# Power.net
KiCad netlist of a schematic drawn in Altium Designer
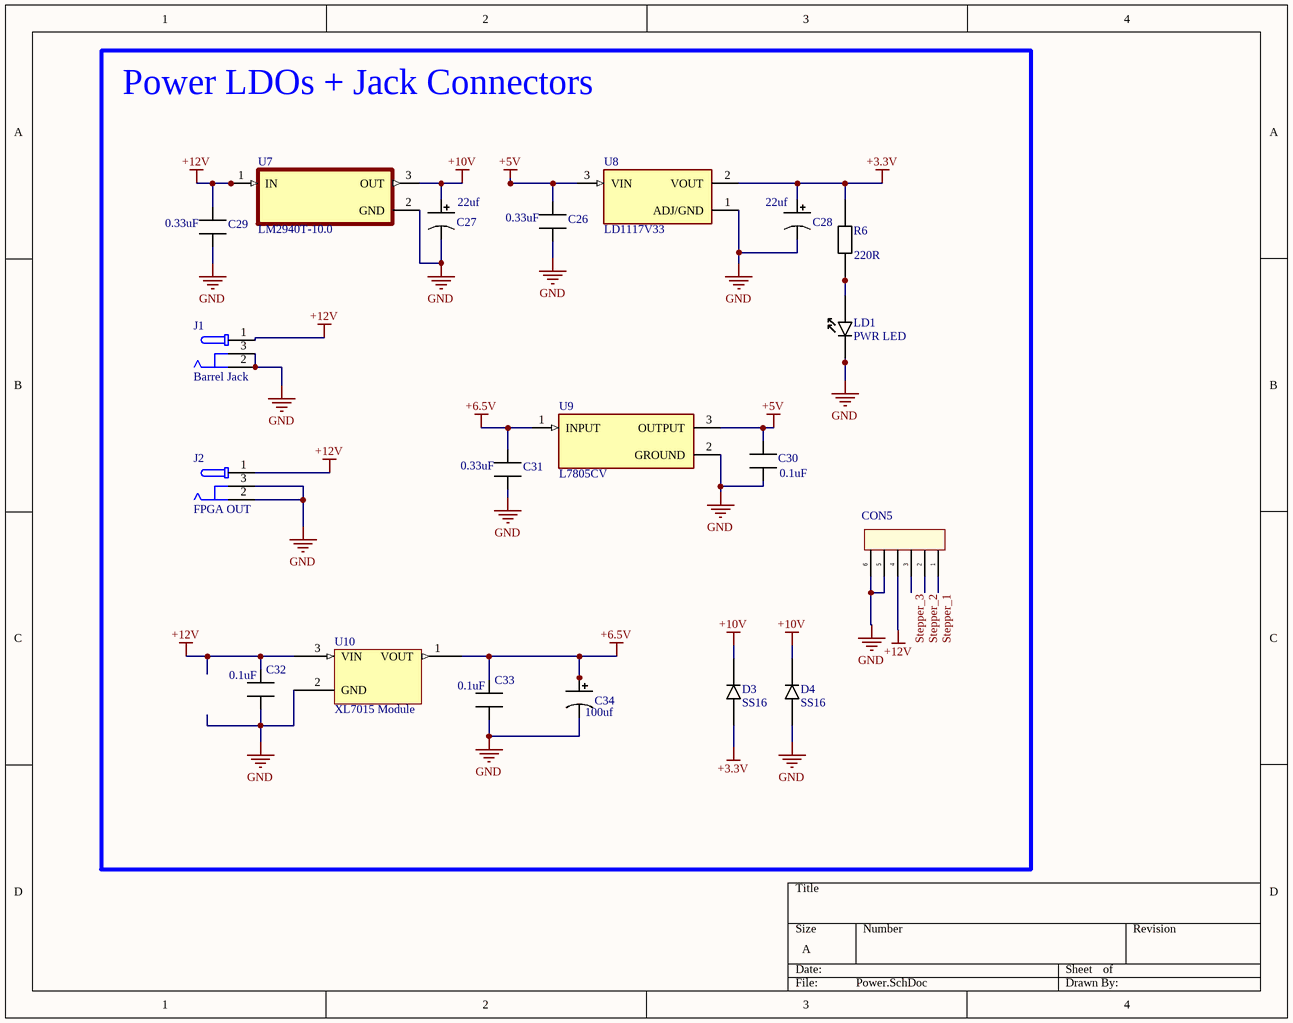
[diagram p0: Power.SchDoc]

(export (version "E")
  (design (tool "Eeschema 10.0.6"))
  (components
    (comp (ref "C26")
      (value "0.33uF")
      (footprint "CAP_0805")
      (description "CAP_0805")
      (fields (field (name "VAL") "0.33uF"))
      (libsource (lib "Passives") (part "CAP_0805"))
    )
    (comp (ref "C27")
      (value "22uf")
      (footprint "CAP_CAN_D5MM")
      (description "SMD Can Capacitor; 5mm Diameter")
      (fields (field (name "VAL") "22uf"))
      (libsource (lib "Passives") (part "CAP_CAN_D5mm"))
    )
    (comp (ref "C28")
      (value "22uf")
      (footprint "CAP_CAN_D5MM")
      (description "SMD Can Capacitor; 5mm Diameter")
      (fields (field (name "VAL") "22uf"))
      (libsource (lib "Passives") (part "CAP_CAN_D5mm"))
    )
    (comp (ref "C29")
      (value "0.33uF")
      (footprint "CAP_0805")
      (description "CAP_0805")
      (fields (field (name "VAL") "0.33uF"))
      (libsource (lib "Passives") (part "CAP_0805"))
    )
    (comp (ref "C30")
      (value "0.1uF")
      (footprint "CAP_0805")
      (description "CAP_0805")
      (fields (field (name "VAL") "0.1uF"))
      (libsource (lib "Passives") (part "CAP_0805"))
    )
    (comp (ref "C31")
      (value "0.33uF")
      (footprint "CAP_0805")
      (description "CAP_0805")
      (fields (field (name "VAL") "0.33uF"))
      (libsource (lib "Passives") (part "CAP_0805"))
    )
    (comp (ref "C32")
      (value "0.1uF")
      (footprint "CAP_0805")
      (description "CAP_0805")
      (fields (field (name "VAL") "0.1uF"))
      (libsource (lib "Passives") (part "CAP_0805"))
    )
    (comp (ref "C33")
      (value "0.1uF")
      (footprint "CAP_0805")
      (description "CAP_0805")
      (fields (field (name "VAL") "0.1uF"))
      (libsource (lib "Passives") (part "CAP_0805"))
    )
    (comp (ref "C34")
      (value "100uf")
      (footprint "CAP_CAN_D5MM")
      (description "SMD Can Capacitor; 5mm Diameter")
      (fields (field (name "VAL") "100uf"))
      (libsource (lib "Passives") (part "CAP_CAN_D5mm"))
    )
    (comp (ref "CON5")
      (value "KF2EDGV-bend-3.81-6p")
      (footprint "CONGREEN_1x6_3.81")
      (libsource (lib "Connectors") (part "CONGREEN_1x6_3.81"))
    )
    (comp (ref "D3")
      (value "SS16")
      (footprint "DO-214AC")
      (description "Independent 60V 700mV@1A 1A SMA(DO-214AC) Single Diodes RoHS")
      (libsource (lib "Diodes") (part "SS16"))
    )
    (comp (ref "D4")
      (value "SS16")
      (footprint "DO-214AC")
      (description "Independent 60V 700mV@1A 1A SMA(DO-214AC) Single Diodes RoHS")
      (libsource (lib "Diodes") (part "SS16"))
    )
    (comp (ref "J1")
      (value "Barrel Jack")
      (footprint "MPD_EJ503A")
      (description "Power Barrel Connector Jack 2.10mm ID (0.083), 5.50mm OD (0.217) Through Hole, Right Angle")
      (fields (field (name "MF") "MPD") (field (name "MP") "EJ503A"))
      (libsource (lib "Connectors") (part "EJ503A"))
    )
    (comp (ref "J2")
      (value "FPGA OUT")
      (footprint "MPD_EJ503A")
      (description "Power Barrel Connector Jack 2.10mm ID (0.083), 5.50mm OD (0.217) Through Hole, Right Angle")
      (fields (field (name "MF") "MPD") (field (name "MP") "EJ503A"))
      (libsource (lib "Connectors") (part "EJ503A"))
    )
    (comp (ref "LD1")
      (value "PWR LED")
      (footprint "LED_0805")
      (description "LED_0805")
      (libsource (lib "Passives") (part "LED_0805"))
    )
    (comp (ref "R6")
      (value "220R")
      (footprint "RES_0805")
      (description "RES_0805")
      (fields (field (name "VAL") "220R"))
      (libsource (lib "Passives") (part "RES_0805"))
    )
    (comp (ref "U7")
      (value "LM2940T-10.0")
      (footprint "TO254P1054X470X1955-3")
      (description "1-A, 26-V, high-PSRR, low-dropout voltage regulator 3-TO-220 -40 to 125")
      (fields (field (name "MF") "Texas Instruments") (field (name "MP") "LM2940T-5.0"))
      (libsource (lib "IC_Power") (part "LM2940T-10.0"))
    )
    (comp (ref "U8")
      (value "LD1117V33")
      (footprint "TO255P1020X450X1968-3")
      (description "Linear Voltage Regulator IC Positive Fixed 1 Output 800mA TO-220AB")
      (fields (field (name "MF") "STMicroelectronics"))
      (libsource (lib "IC_Power") (part "LD1117V33"))
    )
    (comp (ref "U9")
      (value "L7805CV")
      (footprint "TO255P1040X460X1968-3")
      (description "Linear Voltage Regulator IC Positive Fixed 1 Output 1.5A TO-220")
      (fields (field (name "MF") "STMicroelectronics"))
      (libsource (lib "IC_Power") (part "L7805CV"))
    )
    (comp (ref "U10")
      (value "XL7015 Module")
      (footprint "XL7015")
      (description "Buck Converter")
      (libsource (lib "IC_Power") (part "XL7015"))
    )
  )
  (nets
    (net (code "1") (name "+3.3V") (class "Default")
      (node (ref "C28") (pin "1") (pinfunction "1_1") (pintype "passive"))
      (node (ref "D3") (pin "2") (pinfunction "2_2") (pintype "passive"))
      (node (ref "R6") (pin "2") (pinfunction "2_2") (pintype "passive"))
      (node (ref "U8") (pin "2") (pinfunction "VOUT_2") (pintype "power_in"))
    )
    (net (code "2") (name "+5V") (class "Default")
      (node (ref "C26") (pin "2") (pinfunction "2_2") (pintype "passive"))
      (node (ref "C30") (pin "2") (pinfunction "2_2") (pintype "passive"))
      (node (ref "U8") (pin "3") (pinfunction "VIN_3") (pintype "input"))
      (node (ref "U9") (pin "3") (pinfunction "OUTPUT_3") (pintype "power_in"))
    )
    (net (code "3") (name "+6.5V") (class "Default")
      (node (ref "C31") (pin "2") (pinfunction "2_2") (pintype "passive"))
      (node (ref "C33") (pin "2") (pinfunction "2_2") (pintype "passive"))
      (node (ref "C34") (pin "1") (pinfunction "1_1") (pintype "passive"))
      (node (ref "U10") (pin "1") (pinfunction "VOUT_1") (pintype "output"))
      (node (ref "U9") (pin "1") (pinfunction "INPUT_1") (pintype "input"))
    )
    (net (code "4") (name "+10V") (class "Default")
      (node (ref "C27") (pin "1") (pinfunction "1_1") (pintype "passive"))
      (node (ref "D3") (pin "1") (pinfunction "1_1") (pintype "passive"))
      (node (ref "D4") (pin "1") (pinfunction "1_1") (pintype "passive"))
      (node (ref "U7") (pin "3") (pinfunction "OUT_3") (pintype "output"))
    )
    (net (code "5") (name "+12V") (class "Default")
      (node (ref "C29") (pin "2") (pinfunction "2_2") (pintype "passive"))
      (node (ref "C32") (pin "2") (pinfunction "2_2") (pintype "passive"))
      (node (ref "CON5") (pin "4") (pinfunction "4_4") (pintype "passive"))
      (node (ref "J1") (pin "1") (pinfunction "1_1") (pintype "passive"))
      (node (ref "J2") (pin "1") (pinfunction "1_1") (pintype "passive"))
      (node (ref "U10") (pin "3") (pinfunction "VIN_3") (pintype "input"))
      (node (ref "U7") (pin "1") (pinfunction "IN_1") (pintype "input"))
    )
    (net (code "6") (name "/Stepper_1") (class "Default")
      (node (ref "CON5") (pin "1") (pinfunction "1_1") (pintype "passive"))
    )
    (net (code "7") (name "/Stepper_2") (class "Default")
      (node (ref "CON5") (pin "2") (pinfunction "2_2") (pintype "passive"))
    )
    (net (code "8") (name "/Stepper_3") (class "Default")
      (node (ref "CON5") (pin "3") (pinfunction "3_3") (pintype "passive"))
    )
    (net (code "9") (name "GND") (class "Default")
      (node (ref "C26") (pin "1") (pinfunction "1_1") (pintype "passive"))
      (node (ref "C27") (pin "2") (pinfunction "2_2") (pintype "passive"))
      (node (ref "C28") (pin "2") (pinfunction "2_2") (pintype "passive"))
      (node (ref "C29") (pin "1") (pinfunction "1_1") (pintype "passive"))
      (node (ref "C30") (pin "1") (pinfunction "1_1") (pintype "passive"))
      (node (ref "C31") (pin "1") (pinfunction "1_1") (pintype "passive"))
      (node (ref "C32") (pin "1") (pinfunction "1_1") (pintype "passive"))
      (node (ref "C33") (pin "1") (pinfunction "1_1") (pintype "passive"))
      (node (ref "C34") (pin "2") (pinfunction "2_2") (pintype "passive"))
      (node (ref "CON5") (pin "5") (pinfunction "5_5") (pintype "passive"))
      (node (ref "CON5") (pin "6") (pinfunction "6_6") (pintype "passive"))
      (node (ref "D4") (pin "2") (pinfunction "2_2") (pintype "passive"))
      (node (ref "J1") (pin "2") (pinfunction "2_2") (pintype "passive"))
      (node (ref "J1") (pin "3") (pinfunction "3_3") (pintype "passive"))
      (node (ref "J2") (pin "2") (pinfunction "2_2") (pintype "passive"))
      (node (ref "J2") (pin "3") (pinfunction "3_3") (pintype "passive"))
      (node (ref "LD1") (pin "1") (pinfunction "1_1") (pintype "passive"))
      (node (ref "U10") (pin "2") (pinfunction "GND_2") (pintype "passive"))
      (node (ref "U7") (pin "2") (pinfunction "GND_2") (pintype "power_in"))
      (node (ref "U8") (pin "1") (pinfunction "ADJ/GND_1") (pintype "passive"))
      (node (ref "U9") (pin "2") (pinfunction "GROUND_2") (pintype "power_in"))
    )
    (net (code "10") (name "Net-(LD1-Pad2)") (class "Default")
      (node (ref "LD1") (pin "2") (pinfunction "2_2") (pintype "passive"))
      (node (ref "R6") (pin "1") (pinfunction "1_1") (pintype "passive"))
    )
  )
)
